# rfid_accessctl.net
KiCad netlist of a schematic drawn in EAGLE
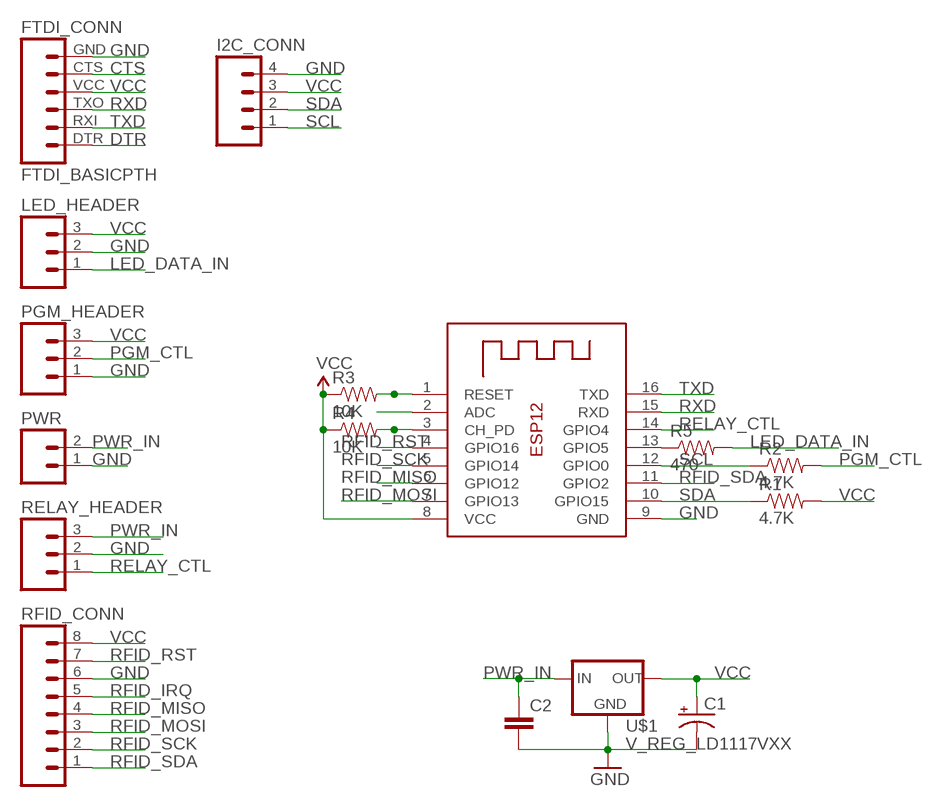
[diagram p0: schematic, sheet 1]

(export (version "E")
  (design (tool "Eeschema 10.0.6"))
  (components
    (comp (ref "C1")
      (value "10UF-25V-20%(PTH)KIT")
      (footprint "eagle-import:CPOL-RADIAL-10UF-25V-KIT")
      (libsource (lib "eagle-import") (part "10UF-25V-20%(PTH)KIT"))
    )
    (comp (ref "C2")
      (value "0.1UF-50V-20%(PTH)KIT-EZ")
      (footprint "eagle-import:CAP-PTH-SMALL-KIT")
      (libsource (lib "eagle-import") (part "0.1UF-50V-20%(PTH)KIT-EZ"))
    )
    (comp (ref "FTDI_CONN")
      (value "FTDI_BASICPTH")
      (footprint "eagle-import:FTDI_BASIC")
      (libsource (lib "eagle-import") (part "FTDI_BASICPTH"))
    )
    (comp (ref "I2C_CONN")
      (value "M04PTH")
      (footprint "eagle-import:1X04")
      (libsource (lib "eagle-import") (part "M04PTH"))
    )
    (comp (ref "LED_HEADER")
      (value "M03PTH")
      (footprint "eagle-import:1X03")
      (libsource (lib "eagle-import") (part "M03PTH"))
    )
    (comp (ref "PGM_HEADER")
      (value "M03PTH")
      (footprint "eagle-import:1X03")
      (libsource (lib "eagle-import") (part "M03PTH"))
    )
    (comp (ref "PWR")
      (value "M02PTH")
      (footprint "eagle-import:1X02")
      (libsource (lib "eagle-import") (part "M02PTH"))
    )
    (comp (ref "R1")
      (value "4.7K")
      (footprint "eagle-import:0603-RES")
      (libsource (lib "eagle-import") (part "10KOHM-1/10W-1%(0603)0603"))
    )
    (comp (ref "R2")
      (value "4.7K")
      (footprint "eagle-import:0603-RES")
      (libsource (lib "eagle-import") (part "10KOHM-1/10W-1%(0603)0603"))
    )
    (comp (ref "R3")
      (value "10K")
      (footprint "eagle-import:0603-RES")
      (libsource (lib "eagle-import") (part "10KOHM-1/10W-1%(0603)0603"))
    )
    (comp (ref "R4")
      (value "10K")
      (footprint "eagle-import:0603-RES")
      (libsource (lib "eagle-import") (part "10KOHM-1/10W-1%(0603)0603"))
    )
    (comp (ref "R5")
      (value "470")
      (footprint "eagle-import:0603-RES")
      (libsource (lib "eagle-import") (part "470OHM1/10W1%(0603)"))
    )
    (comp (ref "RELAY_HEADER")
      (value "M03PTH")
      (footprint "eagle-import:1X03")
      (libsource (lib "eagle-import") (part "M03PTH"))
    )
    (comp (ref "RFID_CONN")
      (value "M08")
      (footprint "eagle-import:1X08_ROUND")
      (libsource (lib "eagle-import") (part "M08"))
    )
    (comp (ref "U$1")
      (value "V_REG_LD1117VXX")
      (footprint "eagle-import:78XXL")
      (libsource (lib "eagle-import") (part "V_REG_LD1117VXX"))
    )
    (comp (ref "X1")
      (value "ESP-12")
      (footprint "eagle-import:ESP-12")
      (libsource (lib "eagle-import") (part "ESP-12"))
    )
  )
  (nets
    (net (code "1") (name "/CTS") (class "Default")
      (node (ref "FTDI_CONN") (pin "CTS") (pinfunction "5_CTS") (pintype "passive"))
    )
    (net (code "2") (name "/DTR") (class "Default")
      (node (ref "FTDI_CONN") (pin "DTR") (pinfunction "1_DTR") (pintype "passive"))
    )
    (net (code "3") (name "/LED_DATA_IN") (class "Default")
      (node (ref "LED_HEADER") (pin "1") (pinfunction "1_1") (pintype "passive"))
      (node (ref "R5") (pin "2") (pinfunction "2_2") (pintype "passive"))
    )
    (net (code "4") (name "/PGM_CTL") (class "Default")
      (node (ref "PGM_HEADER") (pin "2") (pinfunction "2_2") (pintype "passive"))
      (node (ref "R2") (pin "2") (pinfunction "2_2") (pintype "passive"))
    )
    (net (code "5") (name "/PWR_IN") (class "Default")
      (node (ref "C2") (pin "1") (pinfunction "1_1") (pintype "passive"))
      (node (ref "PWR") (pin "2") (pinfunction "2_2") (pintype "passive"))
      (node (ref "RELAY_HEADER") (pin "3") (pinfunction "3_3") (pintype "passive"))
      (node (ref "U$1") (pin "OUT") (pinfunction "IN_OUT") (pintype "input"))
    )
    (net (code "6") (name "/RELAY_CTL") (class "Default")
      (node (ref "RELAY_HEADER") (pin "1") (pinfunction "1_1") (pintype "passive"))
      (node (ref "X1") (pin "14") (pinfunction "GPIO4_14") (pintype "bidirectional"))
    )
    (net (code "7") (name "/RFID_IRQ") (class "Default")
      (node (ref "RFID_CONN") (pin "5") (pinfunction "5_5") (pintype "passive"))
    )
    (net (code "8") (name "/RFID_MISO") (class "Default")
      (node (ref "RFID_CONN") (pin "4") (pinfunction "4_4") (pintype "passive"))
      (node (ref "X1") (pin "6") (pinfunction "GPIO12_6") (pintype "bidirectional"))
    )
    (net (code "9") (name "/RFID_MOSI") (class "Default")
      (node (ref "RFID_CONN") (pin "3") (pinfunction "3_3") (pintype "passive"))
      (node (ref "X1") (pin "7") (pinfunction "GPIO13_7") (pintype "bidirectional"))
    )
    (net (code "10") (name "/RFID_RST") (class "Default")
      (node (ref "RFID_CONN") (pin "7") (pinfunction "7_7") (pintype "passive"))
      (node (ref "X1") (pin "4") (pinfunction "GPIO16_4") (pintype "bidirectional"))
    )
    (net (code "11") (name "/RFID_SCK") (class "Default")
      (node (ref "RFID_CONN") (pin "2") (pinfunction "2_2") (pintype "passive"))
      (node (ref "X1") (pin "5") (pinfunction "GPIO14_5") (pintype "bidirectional"))
    )
    (net (code "12") (name "/RFID_SDA") (class "Default")
      (node (ref "RFID_CONN") (pin "1") (pinfunction "1_1") (pintype "passive"))
      (node (ref "X1") (pin "11") (pinfunction "GPIO2_11") (pintype "bidirectional"))
    )
    (net (code "13") (name "/RXD") (class "Default")
      (node (ref "FTDI_CONN") (pin "TXO") (pinfunction "3_TXO") (pintype "passive"))
      (node (ref "X1") (pin "15") (pinfunction "RXD_15") (pintype "input"))
    )
    (net (code "14") (name "/SCL") (class "Default")
      (node (ref "I2C_CONN") (pin "1") (pinfunction "1_1") (pintype "passive"))
      (node (ref "R2") (pin "1") (pinfunction "1_1") (pintype "passive"))
      (node (ref "X1") (pin "12") (pinfunction "GPIO0_12") (pintype "bidirectional"))
    )
    (net (code "15") (name "/SDA") (class "Default")
      (node (ref "I2C_CONN") (pin "2") (pinfunction "2_2") (pintype "passive"))
      (node (ref "R1") (pin "1") (pinfunction "1_1") (pintype "passive"))
      (node (ref "X1") (pin "10") (pinfunction "GPIO15_10") (pintype "bidirectional"))
    )
    (net (code "16") (name "/TXD") (class "Default")
      (node (ref "FTDI_CONN") (pin "RXI") (pinfunction "2_RXI") (pintype "passive"))
      (node (ref "X1") (pin "16") (pinfunction "TXD_16") (pintype "output"))
    )
    (net (code "17") (name "GND") (class "Default")
      (node (ref "C1") (pin "2") (pinfunction "-_2") (pintype "passive"))
      (node (ref "C2") (pin "2") (pinfunction "2_2") (pintype "passive"))
      (node (ref "FTDI_CONN") (pin "GND") (pinfunction "6_GND") (pintype "passive"))
      (node (ref "I2C_CONN") (pin "4") (pinfunction "4_4") (pintype "passive"))
      (node (ref "LED_HEADER") (pin "2") (pinfunction "2_2") (pintype "passive"))
      (node (ref "PGM_HEADER") (pin "1") (pinfunction "1_1") (pintype "passive"))
      (node (ref "PWR") (pin "1") (pinfunction "1_1") (pintype "passive"))
      (node (ref "RELAY_HEADER") (pin "2") (pinfunction "2_2") (pintype "passive"))
      (node (ref "RFID_CONN") (pin "6") (pinfunction "6_6") (pintype "passive"))
      (node (ref "U$1") (pin "IN") (pinfunction "GND_IN") (pintype "input"))
      (node (ref "X1") (pin "9") (pinfunction "GND_9") (pintype "power_in"))
    )
    (net (code "18") (name "Net-(X1-CH_PD)") (class "Default")
      (node (ref "R4") (pin "2") (pinfunction "2_2") (pintype "passive"))
      (node (ref "X1") (pin "3") (pinfunction "CH_PD_3") (pintype "input"))
    )
    (net (code "19") (name "Net-(X1-GPIO5)") (class "Default")
      (node (ref "R5") (pin "1") (pinfunction "1_1") (pintype "passive"))
      (node (ref "X1") (pin "13") (pinfunction "GPIO5_13") (pintype "bidirectional"))
    )
    (net (code "20") (name "Net-(X1-RESET)") (class "Default")
      (node (ref "R3") (pin "2") (pinfunction "2_2") (pintype "passive"))
      (node (ref "X1") (pin "1") (pinfunction "RESET_1") (pintype "input"))
    )
    (net (code "21") (name "VCC") (class "Default")
      (node (ref "C1") (pin "1") (pinfunction "+_1") (pintype "passive"))
      (node (ref "FTDI_CONN") (pin "VCC") (pinfunction "4_VCC") (pintype "passive"))
      (node (ref "I2C_CONN") (pin "3") (pinfunction "3_3") (pintype "passive"))
      (node (ref "LED_HEADER") (pin "3") (pinfunction "3_3") (pintype "passive"))
      (node (ref "PGM_HEADER") (pin "3") (pinfunction "3_3") (pintype "passive"))
      (node (ref "R1") (pin "2") (pinfunction "2_2") (pintype "passive"))
      (node (ref "R3") (pin "1") (pinfunction "1_1") (pintype "passive"))
      (node (ref "R4") (pin "1") (pinfunction "1_1") (pintype "passive"))
      (node (ref "RFID_CONN") (pin "8") (pinfunction "8_8") (pintype "passive"))
      (node (ref "U$1") (pin "GND") (pinfunction "OUT_GND") (pintype "passive"))
      (node (ref "X1") (pin "8") (pinfunction "VCC_8") (pintype "power_in"))
    )
    (net (code "22") (name "unconnected-(X1-ADC-Pad2)") (class "Default")
      (node (ref "X1") (pin "2") (pinfunction "ADC_2") (pintype "passive"))
    )
  )
)
